# xr_vco_components_manual_rt1.net
KiCad netlist of a schematic drawn in EAGLE
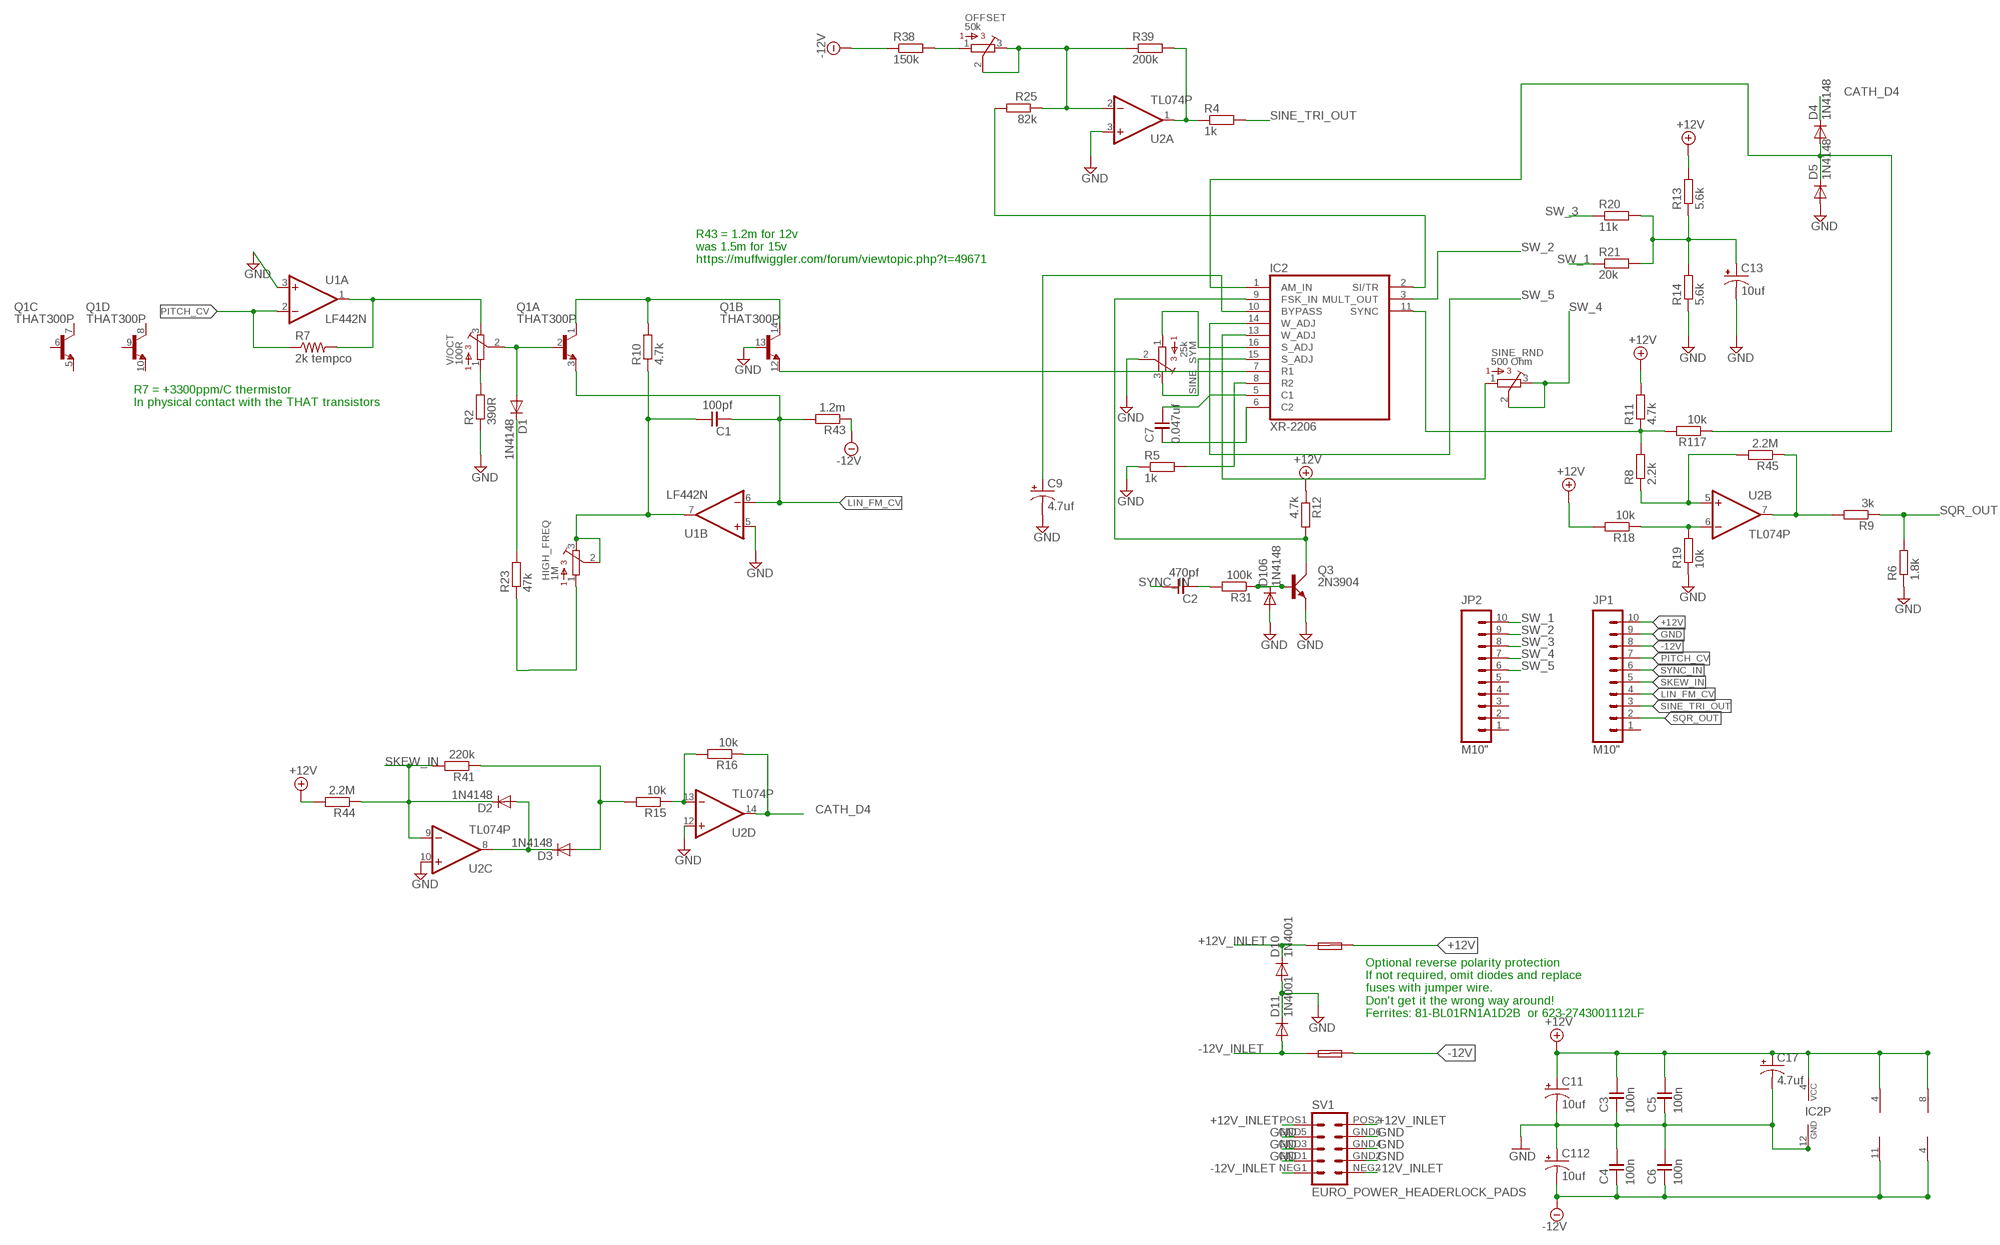
[diagram p0: schematic, sheet 1]

(export (version "E")
  (design (tool "Eeschema 10.0.6"))
  (components
    (comp (ref "C1")
      (value "100pf")
      (footprint "eagle-import:C050-024X044")
      (libsource (lib "eagle-import") (part "C-EU050-024X044"))
    )
    (comp (ref "C2")
      (value "470pf")
      (footprint "eagle-import:C050-024X044")
      (libsource (lib "eagle-import") (part "C-EU050-024X044"))
    )
    (comp (ref "C3")
      (value "100n")
      (footprint "eagle-import:C050-024X044")
      (libsource (lib "eagle-import") (part "C-EU050-024X044"))
    )
    (comp (ref "C4")
      (value "100n")
      (footprint "eagle-import:C050-024X044")
      (libsource (lib "eagle-import") (part "C-EU050-024X044"))
    )
    (comp (ref "C5")
      (value "100n")
      (footprint "eagle-import:C050-024X044")
      (libsource (lib "eagle-import") (part "C-EU050-024X044"))
    )
    (comp (ref "C6")
      (value "100n")
      (footprint "eagle-import:C050-024X044")
      (libsource (lib "eagle-import") (part "C-EU050-024X044"))
    )
    (comp (ref "C7")
      (value "0.047uf")
      (footprint "eagle-import:C050-024X044")
      (libsource (lib "eagle-import") (part "C-EU050-024X044"))
    )
    (comp (ref "C9")
      (value "4.7uf")
      (footprint "eagle-import:CPOL-RADIAL-10UF-25V")
      (libsource (lib "eagle-import") (part "CAP_POLPTH2"))
    )
    (comp (ref "C11")
      (value "10uf")
      (footprint "eagle-import:CPOL-RADIAL-10UF-25V")
      (libsource (lib "eagle-import") (part "CAP_POLPTH2"))
    )
    (comp (ref "C13")
      (value "10uf")
      (footprint "eagle-import:CPOL-RADIAL-10UF-25V")
      (libsource (lib "eagle-import") (part "CAP_POLPTH2"))
    )
    (comp (ref "C17")
      (value "4.7uf")
      (footprint "eagle-import:CPOL-RADIAL-10UF-25V")
      (libsource (lib "eagle-import") (part "CAP_POLPTH2"))
    )
    (comp (ref "C112")
      (value "10uf")
      (footprint "eagle-import:CPOL-RADIAL-10UF-25V")
      (libsource (lib "eagle-import") (part "CAP_POLPTH2"))
    )
    (comp (ref "D1")
      (value "1N4148")
      (footprint "eagle-import:DO35-7")
      (libsource (lib "eagle-import") (part "SMALL_DIODEDO35-7"))
    )
    (comp (ref "D2")
      (value "1N4148")
      (footprint "eagle-import:DO35-7")
      (libsource (lib "eagle-import") (part "SMALL_DIODEDO35-7"))
    )
    (comp (ref "D3")
      (value "1N4148")
      (footprint "eagle-import:DO35-7")
      (libsource (lib "eagle-import") (part "SMALL_DIODEDO35-7"))
    )
    (comp (ref "D4")
      (value "1N4148")
      (footprint "eagle-import:DO35-7")
      (libsource (lib "eagle-import") (part "SMALL_DIODEDO35-7"))
    )
    (comp (ref "D5")
      (value "1N4148")
      (footprint "eagle-import:DO35-7")
      (libsource (lib "eagle-import") (part "SMALL_DIODEDO35-7"))
    )
    (comp (ref "D10")
      (value "1N4001")
      (footprint "eagle-import:DO41-10")
      (libsource (lib "eagle-import") (part "1N4004"))
    )
    (comp (ref "D11")
      (value "1N4001")
      (footprint "eagle-import:DO41-10")
      (libsource (lib "eagle-import") (part "1N4004"))
    )
    (comp (ref "D106")
      (value "1N4148")
      (footprint "eagle-import:DO35-7")
      (libsource (lib "eagle-import") (part "SMALL_DIODEDO35-7"))
    )
    (comp (ref "F1")
      (value "FUSE")
      (footprint "eagle-import:C050H075X075")
      (libsource (lib "eagle-import") (part "PTC_FUSEPOLY_FUSE"))
    )
    (comp (ref "F2")
      (value "FUSE")
      (footprint "eagle-import:C050H075X075")
      (libsource (lib "eagle-import") (part "PTC_FUSEPOLY_FUSE"))
    )
    (comp (ref "HIGH_FREQ")
      (value "1M")
      (footprint "eagle-import:BOURNS_3362P_TRIMMER")
      (libsource (lib "eagle-import") (part "BOURNS_3362P_TRIMMERP"))
    )
    (comp (ref "IC2")
      (value "XR-2206")
      (footprint "eagle-import:DIL16")
      (libsource (lib "eagle-import") (part "XR-2206"))
    )
    (comp (ref "JP1")
      (value "M10\"")
      (footprint "eagle-import:1X10")
      (libsource (lib "eagle-import") (part "M10{dblquote}"))
    )
    (comp (ref "JP2")
      (value "M10\"")
      (footprint "eagle-import:1X10")
      (libsource (lib "eagle-import") (part "M10{dblquote}"))
    )
    (comp (ref "OFFSET")
      (value "50k")
      (footprint "eagle-import:BOURNS_3362P_TRIMMER")
      (libsource (lib "eagle-import") (part "BOURNS_3362P_TRIMMERP"))
    )
    (comp (ref "Q1")
      (value "THAT300P")
      (footprint "eagle-import:DIL14")
      (libsource (lib "eagle-import") (part "THAT300P"))
    )
    (comp (ref "Q3")
      (value "2N3904")
      (footprint "eagle-import:TO92D")
      (libsource (lib "eagle-import") (part "2N3904"))
    )
    (comp (ref "R2")
      (value "390R")
      (footprint "eagle-import:7MM_RESISTOR")
      (libsource (lib "eagle-import") (part "RESISTOR7MM"))
    )
    (comp (ref "R4")
      (value "1k")
      (footprint "eagle-import:7MM_RESISTOR")
      (libsource (lib "eagle-import") (part "RESISTOR7MM"))
    )
    (comp (ref "R5")
      (value "1k")
      (footprint "eagle-import:7MM_RESISTOR")
      (libsource (lib "eagle-import") (part "RESISTOR7MM"))
    )
    (comp (ref "R6")
      (value "1.8k")
      (footprint "eagle-import:7MM_RESISTOR")
      (libsource (lib "eagle-import") (part "RESISTOR7MM"))
    )
    (comp (ref "R7")
      (value "2k tempco")
      (footprint "eagle-import:0309_12")
      (libsource (lib "eagle-import") (part "R-US_0309/12"))
    )
    (comp (ref "R8")
      (value "2.2k")
      (footprint "eagle-import:7MM_RESISTOR")
      (libsource (lib "eagle-import") (part "RESISTOR7MM"))
    )
    (comp (ref "R9")
      (value "3k")
      (footprint "eagle-import:7MM_RESISTOR")
      (libsource (lib "eagle-import") (part "RESISTOR7MM"))
    )
    (comp (ref "R10")
      (value "4.7k")
      (footprint "eagle-import:7MM_RESISTOR")
      (libsource (lib "eagle-import") (part "RESISTOR7MM"))
    )
    (comp (ref "R11")
      (value "4.7k")
      (footprint "eagle-import:7MM_RESISTOR")
      (libsource (lib "eagle-import") (part "RESISTOR7MM"))
    )
    (comp (ref "R12")
      (value "4.7k")
      (footprint "eagle-import:7MM_RESISTOR")
      (libsource (lib "eagle-import") (part "RESISTOR7MM"))
    )
    (comp (ref "R13")
      (value "5.6k")
      (footprint "eagle-import:7MM_RESISTOR")
      (libsource (lib "eagle-import") (part "RESISTOR7MM"))
    )
    (comp (ref "R14")
      (value "5.6k")
      (footprint "eagle-import:7MM_RESISTOR")
      (libsource (lib "eagle-import") (part "RESISTOR7MM"))
    )
    (comp (ref "R15")
      (value "10k")
      (footprint "eagle-import:7MM_RESISTOR")
      (libsource (lib "eagle-import") (part "RESISTOR7MM"))
    )
    (comp (ref "R16")
      (value "10k")
      (footprint "eagle-import:7MM_RESISTOR")
      (libsource (lib "eagle-import") (part "RESISTOR7MM"))
    )
    (comp (ref "R18")
      (value "10k")
      (footprint "eagle-import:7MM_RESISTOR")
      (libsource (lib "eagle-import") (part "RESISTOR7MM"))
    )
    (comp (ref "R19")
      (value "10k")
      (footprint "eagle-import:7MM_RESISTOR")
      (libsource (lib "eagle-import") (part "RESISTOR7MM"))
    )
    (comp (ref "R20")
      (value "11k")
      (footprint "eagle-import:7MM_RESISTOR")
      (libsource (lib "eagle-import") (part "RESISTOR7MM"))
    )
    (comp (ref "R21")
      (value "20k")
      (footprint "eagle-import:7MM_RESISTOR")
      (libsource (lib "eagle-import") (part "RESISTOR7MM"))
    )
    (comp (ref "R23")
      (value "47k")
      (footprint "eagle-import:7MM_RESISTOR")
      (libsource (lib "eagle-import") (part "RESISTOR7MM"))
    )
    (comp (ref "R25")
      (value "82k")
      (footprint "eagle-import:7MM_RESISTOR")
      (libsource (lib "eagle-import") (part "RESISTOR7MM"))
    )
    (comp (ref "R31")
      (value "100k")
      (footprint "eagle-import:7MM_RESISTOR")
      (libsource (lib "eagle-import") (part "RESISTOR7MM"))
    )
    (comp (ref "R38")
      (value "150k")
      (footprint "eagle-import:7MM_RESISTOR")
      (libsource (lib "eagle-import") (part "RESISTOR7MM"))
    )
    (comp (ref "R39")
      (value "200k")
      (footprint "eagle-import:7MM_RESISTOR")
      (libsource (lib "eagle-import") (part "RESISTOR7MM"))
    )
    (comp (ref "R41")
      (value "220k")
      (footprint "eagle-import:7MM_RESISTOR")
      (libsource (lib "eagle-import") (part "RESISTOR7MM"))
    )
    (comp (ref "R43")
      (value "1.2m")
      (footprint "eagle-import:7MM_RESISTOR")
      (libsource (lib "eagle-import") (part "RESISTOR7MM"))
    )
    (comp (ref "R44")
      (value "2.2M")
      (footprint "eagle-import:7MM_RESISTOR")
      (libsource (lib "eagle-import") (part "RESISTOR7MM"))
    )
    (comp (ref "R45")
      (value "2.2M")
      (footprint "eagle-import:7MM_RESISTOR")
      (libsource (lib "eagle-import") (part "RESISTOR7MM"))
    )
    (comp (ref "R117")
      (value "10k")
      (footprint "eagle-import:7MM_RESISTOR")
      (libsource (lib "eagle-import") (part "RESISTOR7MM"))
    )
    (comp (ref "SINE_RND")
      (value "500 Ohm")
      (footprint "eagle-import:BOURNS_3362P_TRIMMER")
      (libsource (lib "eagle-import") (part "BOURNS_3362P_TRIMMERP"))
    )
    (comp (ref "SINE_SYM")
      (value "25k")
      (footprint "eagle-import:BOURNS_3362P_TRIMMER")
      (libsource (lib "eagle-import") (part "BOURNS_3362P_TRIMMERP"))
    )
    (comp (ref "SV1")
      (value "EURO_POWER_HEADERLOCK_PADS")
      (footprint "eagle-import:EURO_PWR_HEADER_LOCK")
      (libsource (lib "eagle-import") (part "EURO_POWER_HEADERLOCK_PADS"))
    )
    (comp (ref "U1")
      (value "LF442N")
      (footprint "eagle-import:DIL08")
      (libsource (lib "eagle-import") (part "LF442N"))
    )
    (comp (ref "U2")
      (value "TL074P")
      (footprint "eagle-import:DIL14")
      (libsource (lib "eagle-import") (part "TL074P"))
    )
    (comp (ref "V/OCT")
      (value "100R")
      (footprint "eagle-import:BOURNS_3362P_TRIMMER")
      (libsource (lib "eagle-import") (part "BOURNS_3362P_TRIMMERP"))
    )
  )
  (nets
    (net (code "1") (name "+12V") (class "Default")
      (node (ref "C11") (pin "1") (pinfunction "+_1") (pintype "passive"))
      (node (ref "C17") (pin "1") (pinfunction "+_1") (pintype "passive"))
      (node (ref "C3") (pin "1") (pinfunction "1_1") (pintype "passive"))
      (node (ref "C5") (pin "1") (pinfunction "1_1") (pintype "passive"))
      (node (ref "F1") (pin "2") (pinfunction "P$2_2") (pintype "bidirectional"))
      (node (ref "IC2") (pin "4") (pinfunction "VCC_4") (pintype "power_in"))
      (node (ref "JP1") (pin "10") (pinfunction "10_10") (pintype "passive"))
      (node (ref "R11") (pin "2") (pinfunction "2_2") (pintype "passive"))
      (node (ref "R12") (pin "1") (pinfunction "1_1") (pintype "passive"))
      (node (ref "R13") (pin "2") (pinfunction "2_2") (pintype "passive"))
      (node (ref "R18") (pin "2") (pinfunction "2_2") (pintype "passive"))
      (node (ref "R44") (pin "2") (pinfunction "2_2") (pintype "passive"))
      (node (ref "U1") (pin "8") (pinfunction "V+_8") (pintype "power_in"))
      (node (ref "U2") (pin "4") (pinfunction "V+_4") (pintype "power_in"))
    )
    (net (code "2") (name "-12V") (class "Default")
      (node (ref "C112") (pin "2") (pinfunction "-_2") (pintype "passive"))
      (node (ref "C4") (pin "2") (pinfunction "2_2") (pintype "passive"))
      (node (ref "C6") (pin "2") (pinfunction "2_2") (pintype "passive"))
      (node (ref "F2") (pin "2") (pinfunction "P$2_2") (pintype "bidirectional"))
      (node (ref "JP1") (pin "8") (pinfunction "8_8") (pintype "passive"))
      (node (ref "R38") (pin "1") (pinfunction "1_1") (pintype "passive"))
      (node (ref "R43") (pin "1") (pinfunction "1_1") (pintype "passive"))
      (node (ref "U1") (pin "4") (pinfunction "V-_4") (pintype "power_in"))
      (node (ref "U2") (pin "11") (pinfunction "V-_11") (pintype "power_in"))
    )
    (net (code "3") (name "/+12V_INLET") (class "Default")
      (node (ref "D10") (pin "C") (pinfunction "C_C") (pintype "passive"))
      (node (ref "F1") (pin "1") (pinfunction "P$1_1") (pintype "bidirectional"))
      (node (ref "SV1") (pin "POS1") (pinfunction "10_POS1") (pintype "passive"))
      (node (ref "SV1") (pin "POS2") (pinfunction "9_POS2") (pintype "passive"))
    )
    (net (code "4") (name "/-12V_INLET") (class "Default")
      (node (ref "D11") (pin "A") (pinfunction "A_A") (pintype "passive"))
      (node (ref "F2") (pin "1") (pinfunction "P$1_1") (pintype "bidirectional"))
      (node (ref "SV1") (pin "NEG1") (pinfunction "2_NEG1") (pintype "passive"))
      (node (ref "SV1") (pin "NEG2") (pinfunction "1_NEG2") (pintype "passive"))
    )
    (net (code "5") (name "/CATH_D4") (class "Default")
      (node (ref "D4") (pin "C") (pinfunction "C_C") (pintype "passive"))
      (node (ref "R16") (pin "1") (pinfunction "1_1") (pintype "passive"))
      (node (ref "U2") (pin "14") (pinfunction "OUT_14") (pintype "output"))
    )
    (net (code "6") (name "/SW_1") (class "Default")
      (node (ref "JP2") (pin "10") (pinfunction "10_10") (pintype "passive"))
      (node (ref "R21") (pin "1") (pinfunction "1_1") (pintype "passive"))
    )
    (net (code "7") (name "/SW_2") (class "Default")
      (node (ref "IC2") (pin "3") (pinfunction "MULT_OUT_3") (pintype "output"))
      (node (ref "JP2") (pin "9") (pinfunction "9_9") (pintype "passive"))
    )
    (net (code "8") (name "/SW_3") (class "Default")
      (node (ref "JP2") (pin "8") (pinfunction "8_8") (pintype "passive"))
      (node (ref "R20") (pin "1") (pinfunction "1_1") (pintype "passive"))
    )
    (net (code "9") (name "/SW_4") (class "Default")
      (node (ref "JP2") (pin "7") (pinfunction "7_7") (pintype "passive"))
      (node (ref "SINE_RND") (pin "2") (pinfunction "2_2") (pintype "passive"))
      (node (ref "SINE_RND") (pin "3") (pinfunction "3_3") (pintype "passive"))
    )
    (net (code "10") (name "/SW_5") (class "Default")
      (node (ref "IC2") (pin "14") (pinfunction "W_ADJ_14") (pintype "input"))
      (node (ref "JP2") (pin "6") (pinfunction "6_6") (pintype "passive"))
    )
    (net (code "11") (name "GND") (class "Default")
      (node (ref "C11") (pin "2") (pinfunction "-_2") (pintype "passive"))
      (node (ref "C112") (pin "1") (pinfunction "+_1") (pintype "passive"))
      (node (ref "C13") (pin "2") (pinfunction "-_2") (pintype "passive"))
      (node (ref "C17") (pin "2") (pinfunction "-_2") (pintype "passive"))
      (node (ref "C3") (pin "2") (pinfunction "2_2") (pintype "passive"))
      (node (ref "C4") (pin "1") (pinfunction "1_1") (pintype "passive"))
      (node (ref "C5") (pin "2") (pinfunction "2_2") (pintype "passive"))
      (node (ref "C6") (pin "1") (pinfunction "1_1") (pintype "passive"))
      (node (ref "C9") (pin "2") (pinfunction "-_2") (pintype "passive"))
      (node (ref "D10") (pin "A") (pinfunction "A_A") (pintype "passive"))
      (node (ref "D106") (pin "A") (pinfunction "A_A") (pintype "passive"))
      (node (ref "D11") (pin "C") (pinfunction "C_C") (pintype "passive"))
      (node (ref "D5") (pin "A") (pinfunction "A_A") (pintype "passive"))
      (node (ref "IC2") (pin "12") (pinfunction "GND_12") (pintype "power_in"))
      (node (ref "JP1") (pin "9") (pinfunction "9_9") (pintype "passive"))
      (node (ref "Q1") (pin "13") (pinfunction "B_13") (pintype "passive"))
      (node (ref "Q3") (pin "E") (pinfunction "E_E") (pintype "passive"))
      (node (ref "R14") (pin "1") (pinfunction "1_1") (pintype "passive"))
      (node (ref "R19") (pin "1") (pinfunction "1_1") (pintype "passive"))
      (node (ref "R2") (pin "1") (pinfunction "1_1") (pintype "passive"))
      (node (ref "R5") (pin "1") (pinfunction "1_1") (pintype "passive"))
      (node (ref "R6") (pin "1") (pinfunction "1_1") (pintype "passive"))
      (node (ref "SINE_SYM") (pin "2") (pinfunction "2_2") (pintype "passive"))
      (node (ref "SV1") (pin "GND1") (pinfunction "4_GND1") (pintype "passive"))
      (node (ref "SV1") (pin "GND2") (pinfunction "3_GND2") (pintype "passive"))
      (node (ref "SV1") (pin "GND3") (pinfunction "6_GND3") (pintype "passive"))
      (node (ref "SV1") (pin "GND4") (pinfunction "5_GND4") (pintype "passive"))
      (node (ref "SV1") (pin "GND5") (pinfunction "8_GND5") (pintype "passive"))
      (node (ref "SV1") (pin "GND6") (pinfunction "7_GND6") (pintype "passive"))
      (node (ref "U1") (pin "3") (pinfunction "+IN_3") (pintype "input"))
      (node (ref "U1") (pin "5") (pinfunction "+IN_5") (pintype "input"))
      (node (ref "U2") (pin "10") (pinfunction "+IN_10") (pintype "input"))
      (node (ref "U2") (pin "12") (pinfunction "+IN_12") (pintype "input"))
      (node (ref "U2") (pin "3") (pinfunction "+IN_3") (pintype "input"))
    )
    (net (code "12") (name "LIN_FM_CV") (class "Default")
      (node (ref "C1") (pin "2") (pinfunction "2_2") (pintype "passive"))
      (node (ref "JP1") (pin "4") (pinfunction "4_4") (pintype "passive"))
      (node (ref "Q1") (pin "3") (pinfunction "E_3") (pintype "passive"))
      (node (ref "R43") (pin "2") (pinfunction "2_2") (pintype "passive"))
      (node (ref "U1") (pin "6") (pinfunction "-IN_6") (pintype "input"))
    )
    (net (code "13") (name "Net-(C2-Pad2)") (class "Default")
      (node (ref "C2") (pin "2") (pinfunction "2_2") (pintype "passive"))
      (node (ref "R31") (pin "2") (pinfunction "2_2") (pintype "passive"))
    )
    (net (code "14") (name "Net-(C9-+)") (class "Default")
      (node (ref "C9") (pin "1") (pinfunction "+_1") (pintype "passive"))
      (node (ref "IC2") (pin "10") (pinfunction "BYPASS_10") (pintype "input"))
    )
    (net (code "15") (name "Net-(C13-+)") (class "Default")
      (node (ref "C13") (pin "1") (pinfunction "+_1") (pintype "passive"))
      (node (ref "R13") (pin "1") (pinfunction "1_1") (pintype "passive"))
      (node (ref "R14") (pin "2") (pinfunction "2_2") (pintype "passive"))
      (node (ref "R20") (pin "2") (pinfunction "2_2") (pintype "passive"))
      (node (ref "R21") (pin "2") (pinfunction "2_2") (pintype "passive"))
    )
    (net (code "16") (name "Net-(D1-PadC)") (class "Default")
      (node (ref "D1") (pin "C") (pinfunction "C_C") (pintype "passive"))
      (node (ref "R23") (pin "2") (pinfunction "2_2") (pintype "passive"))
    )
    (net (code "17") (name "Net-(D3-PadA)") (class "Default")
      (node (ref "D3") (pin "A") (pinfunction "A_A") (pintype "passive"))
      (node (ref "R15") (pin "2") (pinfunction "2_2") (pintype "passive"))
      (node (ref "R41") (pin "1") (pinfunction "1_1") (pintype "passive"))
    )
    (net (code "18") (name "Net-(D106-PadC)") (class "Default")
      (node (ref "D106") (pin "C") (pinfunction "C_C") (pintype "passive"))
      (node (ref "Q3") (pin "B") (pinfunction "B_B") (pintype "passive"))
      (node (ref "R31") (pin "1") (pinfunction "1_1") (pintype "passive"))
    )
    (net (code "19") (name "Net-(HIGH_FREQ-Pad1)") (class "Default")
      (node (ref "HIGH_FREQ") (pin "1") (pinfunction "1_1") (pintype "passive"))
      (node (ref "R23") (pin "1") (pinfunction "1_1") (pintype "passive"))
    )
    (net (code "20") (name "Net-(IC2A-AM_IN)") (class "Default")
      (node (ref "D4") (pin "A") (pinfunction "A_A") (pintype "passive"))
      (node (ref "D5") (pin "C") (pinfunction "C_C") (pintype "passive"))
      (node (ref "IC2") (pin "1") (pinfunction "AM_IN_1") (pintype "input"))
      (node (ref "R117") (pin "1") (pinfunction "1_1") (pintype "passive"))
    )
    (net (code "21") (name "Net-(IC2A-C1)") (class "Default")
      (node (ref "C7") (pin "1") (pinfunction "1_1") (pintype "passive"))
      (node (ref "IC2") (pin "5") (pinfunction "C1_5") (pintype "input"))
    )
    (net (code "22") (name "Net-(IC2A-C2)") (class "Default")
      (node (ref "C7") (pin "2") (pinfunction "2_2") (pintype "passive"))
      (node (ref "IC2") (pin "6") (pinfunction "C2_6") (pintype "input"))
    )
    (net (code "23") (name "Net-(IC2A-FSK_IN)") (class "Default")
      (node (ref "IC2") (pin "9") (pinfunction "FSK_IN_9") (pintype "input"))
      (node (ref "Q3") (pin "C") (pinfunction "C_C") (pintype "passive"))
      (node (ref "R12") (pin "2") (pinfunction "2_2") (pintype "passive"))
    )
    (net (code "24") (name "Net-(IC2A-R1)") (class "Default")
      (node (ref "IC2") (pin "7") (pinfunction "R1_7") (pintype "input"))
      (node (ref "Q1") (pin "12") (pinfunction "E_12") (pintype "passive"))
    )
    (net (code "25") (name "Net-(IC2A-R2)") (class "Default")
      (node (ref "IC2") (pin "8") (pinfunction "R2_8") (pintype "input"))
      (node (ref "R5") (pin "2") (pinfunction "2_2") (pintype "passive"))
    )
    (net (code "26") (name "Net-(IC2A-SI{slash}TR)") (class "Default")
      (node (ref "IC2") (pin "2") (pinfunction "SI/TR_2") (pintype "output"))
      (node (ref "R25") (pin "2") (pinfunction "2_2") (pintype "passive"))
    )
    (net (code "27") (name "Net-(IC2A-SYNC)") (class "Default")
      (node (ref "IC2") (pin "11") (pinfunction "SYNC_11") (pintype "output"))
      (node (ref "R11") (pin "1") (pinfunction "1_1") (pintype "passive"))
      (node (ref "R117") (pin "2") (pinfunction "2_2") (pintype "passive"))
      (node (ref "R8") (pin "2") (pinfunction "2_2") (pintype "passive"))
    )
    (net (code "28") (name "Net-(IC2A-S_ADJ-Pad15)") (class "Default")
      (node (ref "IC2") (pin "15") (pinfunction "S_ADJ_15") (pintype "input"))
      (node (ref "SINE_SYM") (pin "3") (pinfunction "3_3") (pintype "passive"))
    )
    (net (code "29") (name "Net-(IC2A-S_ADJ-Pad16)") (class "Default")
      (node (ref "IC2") (pin "16") (pinfunction "S_ADJ_16") (pintype "input"))
      (node (ref "SINE_SYM") (pin "1") (pinfunction "1_1") (pintype "passive"))
    )
    (net (code "30") (name "Net-(IC2A-W_ADJ-Pad13)") (class "Default")
      (node (ref "IC2") (pin "13") (pinfunction "W_ADJ_13") (pintype "input"))
      (node (ref "SINE_RND") (pin "1") (pinfunction "1_1") (pintype "passive"))
    )
    (net (code "31") (name "Net-(OFFSET-Pad1)") (class "Default")
      (node (ref "OFFSET") (pin "1") (pinfunction "1_1") (pintype "passive"))
      (node (ref "R38") (pin "2") (pinfunction "2_2") (pintype "passive"))
    )
    (net (code "32") (name "Net-(Q1A-B)") (class "Default")
      (node (ref "D1") (pin "A") (pinfunction "A_A") (pintype "passive"))
      (node (ref "Q1") (pin "2") (pinfunction "B_2") (pintype "passive"))
      (node (ref "V/OCT") (pin "2") (pinfunction "2_2") (pintype "passive"))
    )
    (net (code "33") (name "Net-(Q1A-C)") (class "Default")
      (node (ref "Q1") (pin "1") (pinfunction "C_1") (pintype "passive"))
      (node (ref "Q1") (pin "14") (pinfunction "C_14") (pintype "passive"))
      (node (ref "R10") (pin "2") (pinfunction "2_2") (pintype "passive"))
    )
    (net (code "34") (name "Net-(R2-Pad2)") (class "Default")
      (node (ref "R2") (pin "2") (pinfunction "2_2") (pintype "passive"))
      (node (ref "V/OCT") (pin "1") (pinfunction "1_1") (pintype "passive"))
    )
    (net (code "35") (name "Net-(U1A-OUT)") (class "Default")
      (node (ref "R7") (pin "2") (pinfunction "2_2") (pintype "passive"))
      (node (ref "U1") (pin "1") (pinfunction "OUT_1") (pintype "output"))
      (node (ref "V/OCT") (pin "3") (pinfunction "3_3") (pintype "passive"))
    )
    (net (code "36") (name "Net-(U1B-OUT)") (class "Default")
      (node (ref "C1") (pin "1") (pinfunction "1_1") (pintype "passive"))
      (node (ref "HIGH_FREQ") (pin "2") (pinfunction "2_2") (pintype "passive"))
      (node (ref "HIGH_FREQ") (pin "3") (pinfunction "3_3") (pintype "passive"))
      (node (ref "R10") (pin "1") (pinfunction "1_1") (pintype "passive"))
      (node (ref "U1") (pin "7") (pinfunction "OUT_7") (pintype "output"))
    )
    (net (code "37") (name "Net-(U2A--IN)") (class "Default")
      (node (ref "OFFSET") (pin "2") (pinfunction "2_2") (pintype "passive"))
      (node (ref "OFFSET") (pin "3") (pinfunction "3_3") (pintype "passive"))
      (node (ref "R25") (pin "1") (pinfunction "1_1") (pintype "passive"))
      (node (ref "R39") (pin "1") (pinfunction "1_1") (pintype "passive"))
      (node (ref "U2") (pin "2") (pinfunction "-IN_2") (pintype "input"))
    )
    (net (code "38") (name "Net-(U2A-OUT)") (class "Default")
      (node (ref "R39") (pin "2") (pinfunction "2_2") (pintype "passive"))
      (node (ref "R4") (pin "1") (pinfunction "1_1") (pintype "passive"))
      (node (ref "U2") (pin "1") (pinfunction "OUT_1") (pintype "output"))
    )
    (net (code "39") (name "Net-(U2B-+IN)") (class "Default")
      (node (ref "R45") (pin "2") (pinfunction "2_2") (pintype "passive"))
      (node (ref "R8") (pin "1") (pinfunction "1_1") (pintype "passive"))
      (node (ref "U2") (pin "5") (pinfunction "+IN_5") (pintype "input"))
    )
    (net (code "40") (name "Net-(U2B--IN)") (class "Default")
      (node (ref "R18") (pin "1") (pinfunction "1_1") (pintype "passive"))
      (node (ref "R19") (pin "2") (pinfunction "2_2") (pintype "passive"))
      (node (ref "U2") (pin "6") (pinfunction "-IN_6") (pintype "input"))
    )
    (net (code "41") (name "Net-(U2B-OUT)") (class "Default")
      (node (ref "R45") (pin "1") (pinfunction "1_1") (pintype "passive"))
      (node (ref "R9") (pin "2") (pinfunction "2_2") (pintype "passive"))
      (node (ref "U2") (pin "7") (pinfunction "OUT_7") (pintype "output"))
    )
    (net (code "42") (name "Net-(U2C-OUT)") (class "Default")
      (node (ref "D2") (pin "A") (pinfunction "A_A") (pintype "passive"))
      (node (ref "D3") (pin "C") (pinfunction "C_C") (pintype "passive"))
      (node (ref "U2") (pin "8") (pinfunction "OUT_8") (pintype "output"))
    )
    (net (code "43") (name "Net-(U2D--IN)") (class "Default")
      (node (ref "R15") (pin "1") (pinfunction "1_1") (pintype "passive"))
      (node (ref "R16") (pin "2") (pinfunction "2_2") (pintype "passive"))
      (node (ref "U2") (pin "13") (pinfunction "-IN_13") (pintype "input"))
    )
    (net (code "44") (name "PITCH_CV") (class "Default")
      (node (ref "JP1") (pin "7") (pinfunction "7_7") (pintype "passive"))
      (node (ref "R7") (pin "1") (pinfunction "1_1") (pintype "passive"))
      (node (ref "U1") (pin "2") (pinfunction "-IN_2") (pintype "input"))
    )
    (net (code "45") (name "SINE_TRI_OUT") (class "Default")
      (node (ref "JP1") (pin "3") (pinfunction "3_3") (pintype "passive"))
      (node (ref "R4") (pin "2") (pinfunction "2_2") (pintype "passive"))
    )
    (net (code "46") (name "SKEW_IN") (class "Default")
      (node (ref "D2") (pin "C") (pinfunction "C_C") (pintype "passive"))
      (node (ref "JP1") (pin "5") (pinfunction "5_5") (pintype "passive"))
      (node (ref "R41") (pin "2") (pinfunction "2_2") (pintype "passive"))
      (node (ref "R44") (pin "1") (pinfunction "1_1") (pintype "passive"))
      (node (ref "U2") (pin "9") (pinfunction "-IN_9") (pintype "input"))
    )
    (net (code "47") (name "SQR_OUT") (class "Default")
      (node (ref "JP1") (pin "2") (pinfunction "2_2") (pintype "passive"))
      (node (ref "R6") (pin "2") (pinfunction "2_2") (pintype "passive"))
      (node (ref "R9") (pin "1") (pinfunction "1_1") (pintype "passive"))
    )
    (net (code "48") (name "SYNC_IN") (class "Default")
      (node (ref "C2") (pin "1") (pinfunction "1_1") (pintype "passive"))
      (node (ref "JP1") (pin "6") (pinfunction "6_6") (pintype "passive"))
    )
    (net (code "49") (name "unconnected-(JP1-Pad1)") (class "Default")
      (node (ref "JP1") (pin "1") (pinfunction "1_1") (pintype "passive"))
    )
    (net (code "50") (name "unconnected-(JP2-Pad1)") (class "Default")
      (node (ref "JP2") (pin "1") (pinfunction "1_1") (pintype "passive"))
    )
    (net (code "51") (name "unconnected-(JP2-Pad2)") (class "Default")
      (node (ref "JP2") (pin "2") (pinfunction "2_2") (pintype "passive"))
    )
    (net (code "52") (name "unconnected-(JP2-Pad3)") (class "Default")
      (node (ref "JP2") (pin "3") (pinfunction "3_3") (pintype "passive"))
    )
    (net (code "53") (name "unconnected-(JP2-Pad4)") (class "Default")
      (node (ref "JP2") (pin "4") (pinfunction "4_4") (pintype "passive"))
    )
    (net (code "54") (name "unconnected-(JP2-Pad5)") (class "Default")
      (node (ref "JP2") (pin "5") (pinfunction "5_5") (pintype "passive"))
    )
    (net (code "55") (name "unconnected-(Q1C-B-Pad6)") (class "Default")
      (node (ref "Q1") (pin "6") (pinfunction "B_6") (pintype "passive"))
    )
    (net (code "56") (name "unconnected-(Q1C-C-Pad7)") (class "Default")
      (node (ref "Q1") (pin "7") (pinfunction "C_7") (pintype "passive"))
    )
    (net (code "57") (name "unconnected-(Q1C-E-Pad5)") (class "Default")
      (node (ref "Q1") (pin "5") (pinfunction "E_5") (pintype "passive"))
    )
    (net (code "58") (name "unconnected-(Q1D-B-Pad9)") (class "Default")
      (node (ref "Q1") (pin "9") (pinfunction "B_9") (pintype "passive"))
    )
    (net (code "59") (name "unconnected-(Q1D-C-Pad8)") (class "Default")
      (node (ref "Q1") (pin "8") (pinfunction "C_8") (pintype "passive"))
    )
    (net (code "60") (name "unconnected-(Q1D-E-Pad10)") (class "Default")
      (node (ref "Q1") (pin "10") (pinfunction "E_10") (pintype "passive"))
    )
  )
)
